# Mother_Board_Core_Interface.net
KiCad netlist of a schematic drawn in Altium Designer
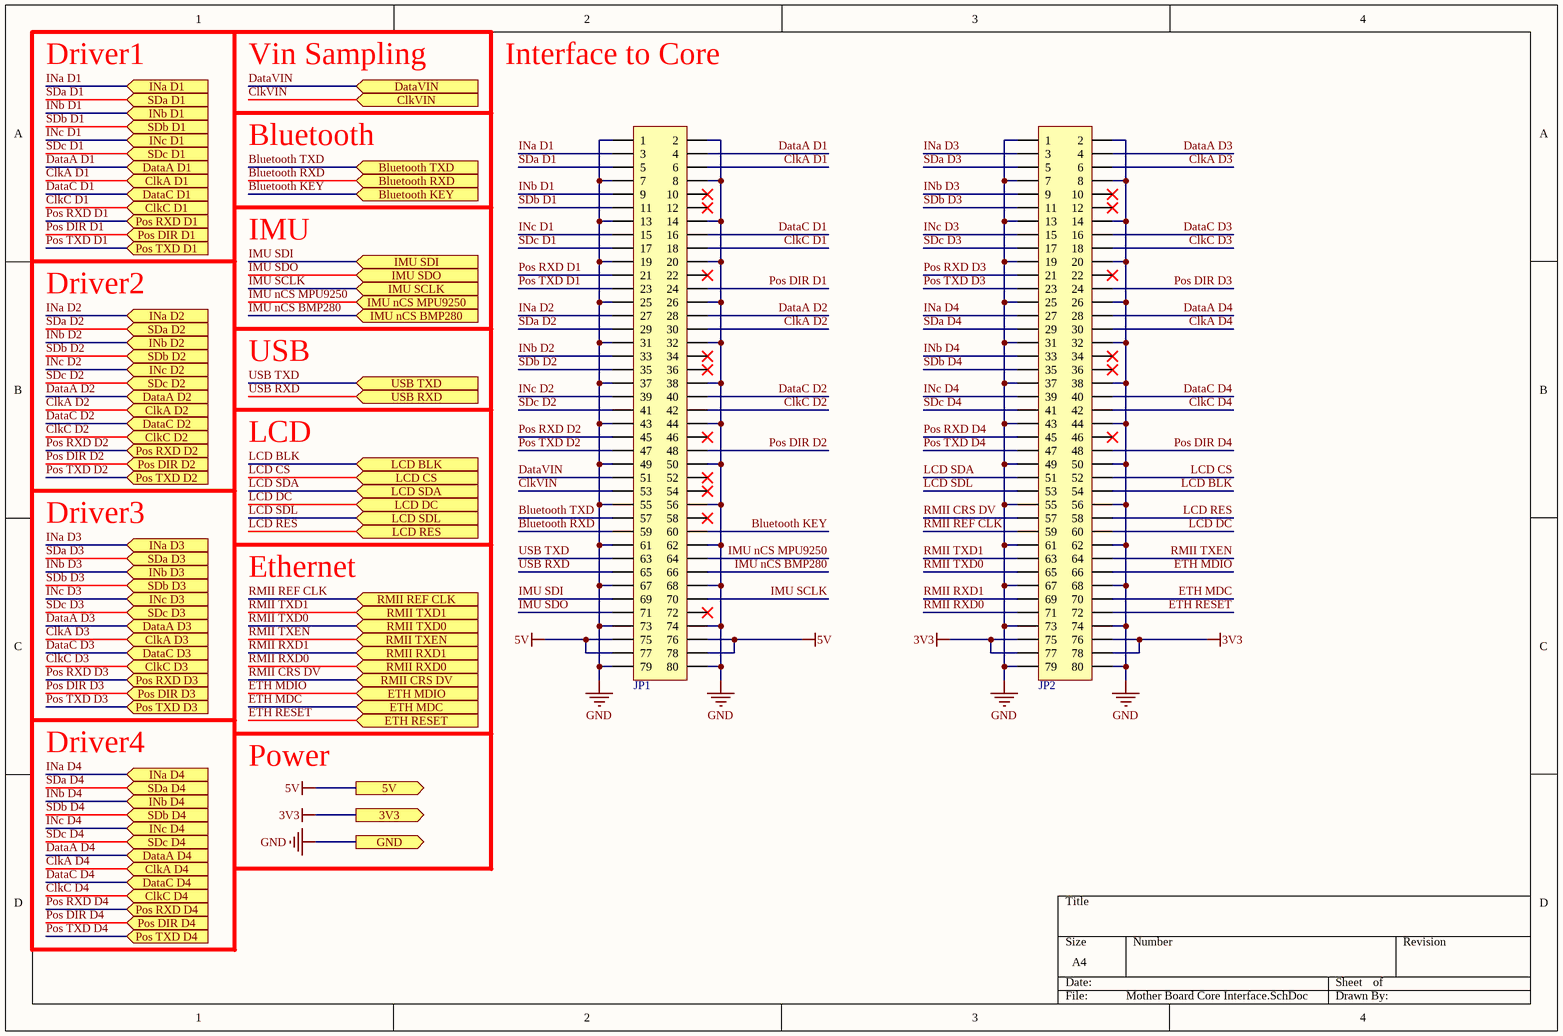
[diagram p0: Mother Board Core Interface.SchDoc]

(export (version "E")
  (design (tool "Eeschema 10.0.6"))
  (components
    (comp (ref "JP1")
      (value "Header 40PX2")
      (footprint "HEADER_0.8mm_2x40P_G")
      (description "40*2P接插件")
      (fields (field (name "版权归属") "源创客"))
      (libsource (lib "All lib") (part "Header 40PX2"))
    )
    (comp (ref "JP2")
      (value "Header 40PX2")
      (footprint "HEADER_0.8mm_2x40P_G")
      (description "40*2P接插件")
      (fields (field (name "版权归属") "源创客"))
      (libsource (lib "All lib") (part "Header 40PX2"))
    )
  )
  (nets
    (net (code "1") (name "/Bluetooth KEY") (class "Default")
      (node (ref "JP1") (pin "60") (pinfunction "60_60") (pintype "passive"))
    )
    (net (code "2") (name "/Bluetooth RXD") (class "Default")
      (node (ref "JP1") (pin "59") (pinfunction "59_59") (pintype "passive"))
    )
    (net (code "3") (name "/Bluetooth TXD") (class "Default")
      (node (ref "JP1") (pin "57") (pinfunction "57_57") (pintype "passive"))
    )
    (net (code "4") (name "/ClkA D1") (class "Default")
      (node (ref "JP1") (pin "6") (pinfunction "6_6") (pintype "passive"))
    )
    (net (code "5") (name "/ClkA D2") (class "Default")
      (node (ref "JP1") (pin "30") (pinfunction "30_30") (pintype "passive"))
    )
    (net (code "6") (name "/ClkA D3") (class "Default")
      (node (ref "JP2") (pin "6") (pinfunction "6_6") (pintype "passive"))
    )
    (net (code "7") (name "/ClkA D4") (class "Default")
      (node (ref "JP2") (pin "30") (pinfunction "30_30") (pintype "passive"))
    )
    (net (code "8") (name "/ClkC D1") (class "Default")
      (node (ref "JP1") (pin "18") (pinfunction "18_18") (pintype "passive"))
    )
    (net (code "9") (name "/ClkC D2") (class "Default")
      (node (ref "JP1") (pin "42") (pinfunction "42_42") (pintype "passive"))
    )
    (net (code "10") (name "/ClkC D3") (class "Default")
      (node (ref "JP2") (pin "18") (pinfunction "18_18") (pintype "passive"))
    )
    (net (code "11") (name "/ClkC D4") (class "Default")
      (node (ref "JP2") (pin "42") (pinfunction "42_42") (pintype "passive"))
    )
    (net (code "12") (name "/ClkVIN") (class "Default")
      (node (ref "JP1") (pin "53") (pinfunction "53_53") (pintype "passive"))
    )
    (net (code "13") (name "/DataA D1") (class "Default")
      (node (ref "JP1") (pin "4") (pinfunction "4_4") (pintype "passive"))
    )
    (net (code "14") (name "/DataA D2") (class "Default")
      (node (ref "JP1") (pin "28") (pinfunction "28_28") (pintype "passive"))
    )
    (net (code "15") (name "/DataA D3") (class "Default")
      (node (ref "JP2") (pin "4") (pinfunction "4_4") (pintype "passive"))
    )
    (net (code "16") (name "/DataA D4") (class "Default")
      (node (ref "JP2") (pin "28") (pinfunction "28_28") (pintype "passive"))
    )
    (net (code "17") (name "/DataC D1") (class "Default")
      (node (ref "JP1") (pin "16") (pinfunction "16_16") (pintype "passive"))
    )
    (net (code "18") (name "/DataC D2") (class "Default")
      (node (ref "JP1") (pin "40") (pinfunction "40_40") (pintype "passive"))
    )
    (net (code "19") (name "/DataC D3") (class "Default")
      (node (ref "JP2") (pin "16") (pinfunction "16_16") (pintype "passive"))
    )
    (net (code "20") (name "/DataC D4") (class "Default")
      (node (ref "JP2") (pin "40") (pinfunction "40_40") (pintype "passive"))
    )
    (net (code "21") (name "/DataVIN") (class "Default")
      (node (ref "JP1") (pin "51") (pinfunction "51_51") (pintype "passive"))
    )
    (net (code "22") (name "/ETH MDC") (class "Default")
      (node (ref "JP2") (pin "70") (pinfunction "70_70") (pintype "passive"))
    )
    (net (code "23") (name "/ETH MDIO") (class "Default")
      (node (ref "JP2") (pin "66") (pinfunction "66_66") (pintype "passive"))
    )
    (net (code "24") (name "/ETH RESET") (class "Default")
      (node (ref "JP2") (pin "72") (pinfunction "72_72") (pintype "passive"))
    )
    (net (code "25") (name "/IMU SCLK") (class "Default")
      (node (ref "JP1") (pin "70") (pinfunction "70_70") (pintype "passive"))
    )
    (net (code "26") (name "/IMU SDI") (class "Default")
      (node (ref "JP1") (pin "69") (pinfunction "69_69") (pintype "passive"))
    )
    (net (code "27") (name "/IMU SDO") (class "Default")
      (node (ref "JP1") (pin "71") (pinfunction "71_71") (pintype "passive"))
    )
    (net (code "28") (name "/IMU nCS BMP280") (class "Default")
      (node (ref "JP1") (pin "66") (pinfunction "66_66") (pintype "passive"))
    )
    (net (code "29") (name "/IMU nCS MPU9250") (class "Default")
      (node (ref "JP1") (pin "64") (pinfunction "64_64") (pintype "passive"))
    )
    (net (code "30") (name "/INa D1") (class "Default")
      (node (ref "JP1") (pin "3") (pinfunction "3_3") (pintype "passive"))
    )
    (net (code "31") (name "/INa D2") (class "Default")
      (node (ref "JP1") (pin "27") (pinfunction "27_27") (pintype "passive"))
    )
    (net (code "32") (name "/INa D3") (class "Default")
      (node (ref "JP2") (pin "3") (pinfunction "3_3") (pintype "passive"))
    )
    (net (code "33") (name "/INa D4") (class "Default")
      (node (ref "JP2") (pin "27") (pinfunction "27_27") (pintype "passive"))
    )
    (net (code "34") (name "/INb D1") (class "Default")
      (node (ref "JP1") (pin "9") (pinfunction "9_9") (pintype "passive"))
    )
    (net (code "35") (name "/INb D2") (class "Default")
      (node (ref "JP1") (pin "33") (pinfunction "33_33") (pintype "passive"))
    )
    (net (code "36") (name "/INb D3") (class "Default")
      (node (ref "JP2") (pin "9") (pinfunction "9_9") (pintype "passive"))
    )
    (net (code "37") (name "/INb D4") (class "Default")
      (node (ref "JP2") (pin "33") (pinfunction "33_33") (pintype "passive"))
    )
    (net (code "38") (name "/INc D1") (class "Default")
      (node (ref "JP1") (pin "15") (pinfunction "15_15") (pintype "passive"))
    )
    (net (code "39") (name "/INc D2") (class "Default")
      (node (ref "JP1") (pin "39") (pinfunction "39_39") (pintype "passive"))
    )
    (net (code "40") (name "/INc D3") (class "Default")
      (node (ref "JP2") (pin "15") (pinfunction "15_15") (pintype "passive"))
    )
    (net (code "41") (name "/INc D4") (class "Default")
      (node (ref "JP2") (pin "39") (pinfunction "39_39") (pintype "passive"))
    )
    (net (code "42") (name "/LCD BLK") (class "Default")
      (node (ref "JP2") (pin "54") (pinfunction "54_54") (pintype "passive"))
    )
    (net (code "43") (name "/LCD CS") (class "Default")
      (node (ref "JP2") (pin "52") (pinfunction "52_52") (pintype "passive"))
    )
    (net (code "44") (name "/LCD DC") (class "Default")
      (node (ref "JP2") (pin "60") (pinfunction "60_60") (pintype "passive"))
    )
    (net (code "45") (name "/LCD RES") (class "Default")
      (node (ref "JP2") (pin "58") (pinfunction "58_58") (pintype "passive"))
    )
    (net (code "46") (name "/LCD SDA") (class "Default")
      (node (ref "JP2") (pin "51") (pinfunction "51_51") (pintype "passive"))
    )
    (net (code "47") (name "/LCD SDL") (class "Default")
      (node (ref "JP2") (pin "53") (pinfunction "53_53") (pintype "passive"))
    )
    (net (code "48") (name "/Pos DIR D1") (class "Default")
      (node (ref "JP1") (pin "24") (pinfunction "24_24") (pintype "passive"))
    )
    (net (code "49") (name "/Pos DIR D2") (class "Default")
      (node (ref "JP1") (pin "48") (pinfunction "48_48") (pintype "passive"))
    )
    (net (code "50") (name "/Pos DIR D3") (class "Default")
      (node (ref "JP2") (pin "24") (pinfunction "24_24") (pintype "passive"))
    )
    (net (code "51") (name "/Pos DIR D4") (class "Default")
      (node (ref "JP2") (pin "48") (pinfunction "48_48") (pintype "passive"))
    )
    (net (code "52") (name "/Pos RXD D1") (class "Default")
      (node (ref "JP1") (pin "21") (pinfunction "21_21") (pintype "passive"))
    )
    (net (code "53") (name "/Pos RXD D2") (class "Default")
      (node (ref "JP1") (pin "45") (pinfunction "45_45") (pintype "passive"))
    )
    (net (code "54") (name "/Pos RXD D3") (class "Default")
      (node (ref "JP2") (pin "21") (pinfunction "21_21") (pintype "passive"))
    )
    (net (code "55") (name "/Pos RXD D4") (class "Default")
      (node (ref "JP2") (pin "45") (pinfunction "45_45") (pintype "passive"))
    )
    (net (code "56") (name "/Pos TXD D1") (class "Default")
      (node (ref "JP1") (pin "23") (pinfunction "23_23") (pintype "passive"))
    )
    (net (code "57") (name "/Pos TXD D2") (class "Default")
      (node (ref "JP1") (pin "47") (pinfunction "47_47") (pintype "passive"))
    )
    (net (code "58") (name "/Pos TXD D3") (class "Default")
      (node (ref "JP2") (pin "23") (pinfunction "23_23") (pintype "passive"))
    )
    (net (code "59") (name "/Pos TXD D4") (class "Default")
      (node (ref "JP2") (pin "47") (pinfunction "47_47") (pintype "passive"))
    )
    (net (code "60") (name "/RMII CRS DV") (class "Default")
      (node (ref "JP2") (pin "57") (pinfunction "57_57") (pintype "passive"))
    )
    (net (code "61") (name "/RMII REF CLK") (class "Default")
      (node (ref "JP2") (pin "59") (pinfunction "59_59") (pintype "passive"))
    )
    (net (code "62") (name "/RMII RXD0") (class "Default")
      (node (ref "JP2") (pin "71") (pinfunction "71_71") (pintype "passive"))
    )
    (net (code "63") (name "/RMII RXD1") (class "Default")
      (node (ref "JP2") (pin "69") (pinfunction "69_69") (pintype "passive"))
    )
    (net (code "64") (name "/RMII TXD0") (class "Default")
      (node (ref "JP2") (pin "65") (pinfunction "65_65") (pintype "passive"))
    )
    (net (code "65") (name "/RMII TXD1") (class "Default")
      (node (ref "JP2") (pin "63") (pinfunction "63_63") (pintype "passive"))
    )
    (net (code "66") (name "/RMII TXEN") (class "Default")
      (node (ref "JP2") (pin "64") (pinfunction "64_64") (pintype "passive"))
    )
    (net (code "67") (name "/SDa D1") (class "Default")
      (node (ref "JP1") (pin "5") (pinfunction "5_5") (pintype "passive"))
    )
    (net (code "68") (name "/SDa D2") (class "Default")
      (node (ref "JP1") (pin "29") (pinfunction "29_29") (pintype "passive"))
    )
    (net (code "69") (name "/SDa D3") (class "Default")
      (node (ref "JP2") (pin "5") (pinfunction "5_5") (pintype "passive"))
    )
    (net (code "70") (name "/SDa D4") (class "Default")
      (node (ref "JP2") (pin "29") (pinfunction "29_29") (pintype "passive"))
    )
    (net (code "71") (name "/SDb D1") (class "Default")
      (node (ref "JP1") (pin "11") (pinfunction "11_11") (pintype "passive"))
    )
    (net (code "72") (name "/SDb D2") (class "Default")
      (node (ref "JP1") (pin "35") (pinfunction "35_35") (pintype "passive"))
    )
    (net (code "73") (name "/SDb D3") (class "Default")
      (node (ref "JP2") (pin "11") (pinfunction "11_11") (pintype "passive"))
    )
    (net (code "74") (name "/SDb D4") (class "Default")
      (node (ref "JP2") (pin "35") (pinfunction "35_35") (pintype "passive"))
    )
    (net (code "75") (name "/SDc D1") (class "Default")
      (node (ref "JP1") (pin "17") (pinfunction "17_17") (pintype "passive"))
    )
    (net (code "76") (name "/SDc D2") (class "Default")
      (node (ref "JP1") (pin "41") (pinfunction "41_41") (pintype "passive"))
    )
    (net (code "77") (name "/SDc D3") (class "Default")
      (node (ref "JP2") (pin "17") (pinfunction "17_17") (pintype "passive"))
    )
    (net (code "78") (name "/SDc D4") (class "Default")
      (node (ref "JP2") (pin "41") (pinfunction "41_41") (pintype "passive"))
    )
    (net (code "79") (name "/USB RXD") (class "Default")
      (node (ref "JP1") (pin "65") (pinfunction "65_65") (pintype "passive"))
    )
    (net (code "80") (name "/USB TXD") (class "Default")
      (node (ref "JP1") (pin "63") (pinfunction "63_63") (pintype "passive"))
    )
    (net (code "81") (name "3V3") (class "Default")
      (node (ref "JP2") (pin "75") (pinfunction "75_75") (pintype "passive"))
      (node (ref "JP2") (pin "76") (pinfunction "76_76") (pintype "passive"))
      (node (ref "JP2") (pin "77") (pinfunction "77_77") (pintype "passive"))
      (node (ref "JP2") (pin "78") (pinfunction "78_78") (pintype "passive"))
    )
    (net (code "82") (name "5V") (class "Default")
      (node (ref "JP1") (pin "75") (pinfunction "75_75") (pintype "passive"))
      (node (ref "JP1") (pin "76") (pinfunction "76_76") (pintype "passive"))
      (node (ref "JP1") (pin "77") (pinfunction "77_77") (pintype "passive"))
      (node (ref "JP1") (pin "78") (pinfunction "78_78") (pintype "passive"))
    )
    (net (code "83") (name "GND") (class "Default")
      (node (ref "JP1") (pin "1") (pinfunction "1_1") (pintype "passive"))
      (node (ref "JP1") (pin "13") (pinfunction "13_13") (pintype "passive"))
      (node (ref "JP1") (pin "14") (pinfunction "14_14") (pintype "passive"))
      (node (ref "JP1") (pin "19") (pinfunction "19_19") (pintype "passive"))
      (node (ref "JP1") (pin "2") (pinfunction "2_2") (pintype "passive"))
      (node (ref "JP1") (pin "20") (pinfunction "20_20") (pintype "passive"))
      (node (ref "JP1") (pin "25") (pinfunction "25_25") (pintype "passive"))
      (node (ref "JP1") (pin "26") (pinfunction "26_26") (pintype "passive"))
      (node (ref "JP1") (pin "31") (pinfunction "31_31") (pintype "passive"))
      (node (ref "JP1") (pin "32") (pinfunction "32_32") (pintype "passive"))
      (node (ref "JP1") (pin "37") (pinfunction "37_37") (pintype "passive"))
      (node (ref "JP1") (pin "38") (pinfunction "38_38") (pintype "passive"))
      (node (ref "JP1") (pin "43") (pinfunction "43_43") (pintype "passive"))
      (node (ref "JP1") (pin "44") (pinfunction "44_44") (pintype "passive"))
      (node (ref "JP1") (pin "49") (pinfunction "49_49") (pintype "passive"))
      (node (ref "JP1") (pin "50") (pinfunction "50_50") (pintype "passive"))
      (node (ref "JP1") (pin "55") (pinfunction "55_55") (pintype "passive"))
      (node (ref "JP1") (pin "56") (pinfunction "56_56") (pintype "passive"))
      (node (ref "JP1") (pin "61") (pinfunction "61_61") (pintype "passive"))
      (node (ref "JP1") (pin "62") (pinfunction "62_62") (pintype "passive"))
      (node (ref "JP1") (pin "67") (pinfunction "67_67") (pintype "passive"))
      (node (ref "JP1") (pin "68") (pinfunction "68_68") (pintype "passive"))
      (node (ref "JP1") (pin "7") (pinfunction "7_7") (pintype "passive"))
      (node (ref "JP1") (pin "73") (pinfunction "73_73") (pintype "passive"))
      (node (ref "JP1") (pin "74") (pinfunction "74_74") (pintype "passive"))
      (node (ref "JP1") (pin "79") (pinfunction "79_79") (pintype "passive"))
      (node (ref "JP1") (pin "8") (pinfunction "8_8") (pintype "passive"))
      (node (ref "JP1") (pin "80") (pinfunction "80_80") (pintype "passive"))
      (node (ref "JP2") (pin "1") (pinfunction "1_1") (pintype "passive"))
      (node (ref "JP2") (pin "13") (pinfunction "13_13") (pintype "passive"))
      (node (ref "JP2") (pin "14") (pinfunction "14_14") (pintype "passive"))
      (node (ref "JP2") (pin "19") (pinfunction "19_19") (pintype "passive"))
      (node (ref "JP2") (pin "2") (pinfunction "2_2") (pintype "passive"))
      (node (ref "JP2") (pin "20") (pinfunction "20_20") (pintype "passive"))
      (node (ref "JP2") (pin "25") (pinfunction "25_25") (pintype "passive"))
      (node (ref "JP2") (pin "26") (pinfunction "26_26") (pintype "passive"))
      (node (ref "JP2") (pin "31") (pinfunction "31_31") (pintype "passive"))
      (node (ref "JP2") (pin "32") (pinfunction "32_32") (pintype "passive"))
      (node (ref "JP2") (pin "37") (pinfunction "37_37") (pintype "passive"))
      (node (ref "JP2") (pin "38") (pinfunction "38_38") (pintype "passive"))
      (node (ref "JP2") (pin "43") (pinfunction "43_43") (pintype "passive"))
      (node (ref "JP2") (pin "44") (pinfunction "44_44") (pintype "passive"))
      (node (ref "JP2") (pin "49") (pinfunction "49_49") (pintype "passive"))
      (node (ref "JP2") (pin "50") (pinfunction "50_50") (pintype "passive"))
      (node (ref "JP2") (pin "55") (pinfunction "55_55") (pintype "passive"))
      (node (ref "JP2") (pin "56") (pinfunction "56_56") (pintype "passive"))
      (node (ref "JP2") (pin "61") (pinfunction "61_61") (pintype "passive"))
      (node (ref "JP2") (pin "62") (pinfunction "62_62") (pintype "passive"))
      (node (ref "JP2") (pin "67") (pinfunction "67_67") (pintype "passive"))
      (node (ref "JP2") (pin "68") (pinfunction "68_68") (pintype "passive"))
      (node (ref "JP2") (pin "7") (pinfunction "7_7") (pintype "passive"))
      (node (ref "JP2") (pin "73") (pinfunction "73_73") (pintype "passive"))
      (node (ref "JP2") (pin "74") (pinfunction "74_74") (pintype "passive"))
      (node (ref "JP2") (pin "79") (pinfunction "79_79") (pintype "passive"))
      (node (ref "JP2") (pin "8") (pinfunction "8_8") (pintype "passive"))
      (node (ref "JP2") (pin "80") (pinfunction "80_80") (pintype "passive"))
    )
    (net (code "84") (name "unconnected-(JP1-Pad10)") (class "Default")
      (node (ref "JP1") (pin "10") (pinfunction "10_10") (pintype "passive+no_connect"))
    )
    (net (code "85") (name "unconnected-(JP1-Pad12)") (class "Default")
      (node (ref "JP1") (pin "12") (pinfunction "12_12") (pintype "passive+no_connect"))
    )
    (net (code "86") (name "unconnected-(JP1-Pad22)") (class "Default")
      (node (ref "JP1") (pin "22") (pinfunction "22_22") (pintype "passive+no_connect"))
    )
    (net (code "87") (name "unconnected-(JP1-Pad34)") (class "Default")
      (node (ref "JP1") (pin "34") (pinfunction "34_34") (pintype "passive+no_connect"))
    )
    (net (code "88") (name "unconnected-(JP1-Pad36)") (class "Default")
      (node (ref "JP1") (pin "36") (pinfunction "36_36") (pintype "passive+no_connect"))
    )
    (net (code "89") (name "unconnected-(JP1-Pad46)") (class "Default")
      (node (ref "JP1") (pin "46") (pinfunction "46_46") (pintype "passive+no_connect"))
    )
    (net (code "90") (name "unconnected-(JP1-Pad52)") (class "Default")
      (node (ref "JP1") (pin "52") (pinfunction "52_52") (pintype "passive+no_connect"))
    )
    (net (code "91") (name "unconnected-(JP1-Pad54)") (class "Default")
      (node (ref "JP1") (pin "54") (pinfunction "54_54") (pintype "passive+no_connect"))
    )
    (net (code "92") (name "unconnected-(JP1-Pad58)") (class "Default")
      (node (ref "JP1") (pin "58") (pinfunction "58_58") (pintype "passive+no_connect"))
    )
    (net (code "93") (name "unconnected-(JP1-Pad72)") (class "Default")
      (node (ref "JP1") (pin "72") (pinfunction "72_72") (pintype "passive+no_connect"))
    )
    (net (code "94") (name "unconnected-(JP2-Pad10)") (class "Default")
      (node (ref "JP2") (pin "10") (pinfunction "10_10") (pintype "passive+no_connect"))
    )
    (net (code "95") (name "unconnected-(JP2-Pad12)") (class "Default")
      (node (ref "JP2") (pin "12") (pinfunction "12_12") (pintype "passive+no_connect"))
    )
    (net (code "96") (name "unconnected-(JP2-Pad22)") (class "Default")
      (node (ref "JP2") (pin "22") (pinfunction "22_22") (pintype "passive+no_connect"))
    )
    (net (code "97") (name "unconnected-(JP2-Pad34)") (class "Default")
      (node (ref "JP2") (pin "34") (pinfunction "34_34") (pintype "passive+no_connect"))
    )
    (net (code "98") (name "unconnected-(JP2-Pad36)") (class "Default")
      (node (ref "JP2") (pin "36") (pinfunction "36_36") (pintype "passive+no_connect"))
    )
    (net (code "99") (name "unconnected-(JP2-Pad46)") (class "Default")
      (node (ref "JP2") (pin "46") (pinfunction "46_46") (pintype "passive+no_connect"))
    )
  )
)
